# USB3_Controller_Schematics.net
KiCad netlist of a schematic drawn in Altium Designer
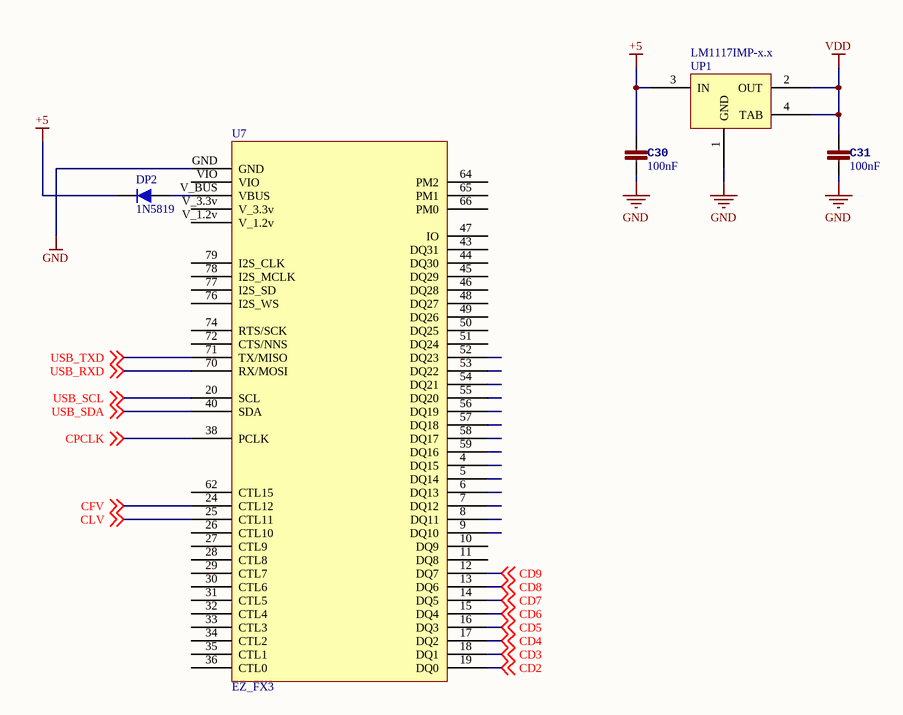
[diagram p0: USB3_Controller_Schematics.SchDoc]

(export (version "E")
  (design (tool "Eeschema 10.0.6"))
  (components
    (comp (ref "C30")
      (value "100nF")
      (footprint "_0805")
      (fields (field (name "Comment") "Cap"))
      (libsource (lib "Passives_Integrated_Library") (part "Cap_1"))
    )
    (comp (ref "C31")
      (value "100nF")
      (footprint "_0805")
      (fields (field (name "Comment") "Cap"))
      (libsource (lib "Passives_Integrated_Library") (part "Cap_1"))
    )
    (comp (ref "DP2")
      (value "1N5819")
      (footprint "430X270D")
      (description "Schottkey Rectifiers")
      (fields (field (name "DESIGNER") "Abbas Basereh"))
      (libsource (lib "Diodes_Integrated_Library") (part "1N5819"))
    )
    (comp (ref "U7")
      (value "EZ_FX3")
      (footprint "EZ_FX3")
      (libsource (lib "Boards_ans_moduls_Integrated_Library") (part "EZ_FX3"))
    )
    (comp (ref "UP1")
      (value "LM1117IMP-x.x")
      (footprint "SOT223_4")
      (description "x.x Volt, 800mA Low-Dropout Linear Regulator, 4-pin SOT-223")
      (fields (field (name "DESIGNER") "Abbas Basereh"))
      (libsource (lib "Regulators_Integrated_Library") (part "LM1117IMP-x.x"))
    )
  )
  (nets
    (net (code "1") (name "+5") (class "Default")
      (node (ref "C30") (pin "1") (pinfunction "1_1") (pintype "passive"))
      (node (ref "DP2") (pin "2") (pintype "passive"))
      (node (ref "UP1") (pin "3") (pinfunction "IN_3") (pintype "power_in"))
    )
    (net (code "2") (name "CD2") (class "Default")
      (node (ref "U7") (pin "19") (pinfunction "DQ0_19") (pintype "passive"))
    )
    (net (code "3") (name "CD3") (class "Default")
      (node (ref "U7") (pin "18") (pinfunction "DQ1_18") (pintype "passive"))
    )
    (net (code "4") (name "CD4") (class "Default")
      (node (ref "U7") (pin "17") (pinfunction "DQ2_17") (pintype "passive"))
    )
    (net (code "5") (name "CD5") (class "Default")
      (node (ref "U7") (pin "16") (pinfunction "DQ3_16") (pintype "passive"))
    )
    (net (code "6") (name "CD6") (class "Default")
      (node (ref "U7") (pin "15") (pinfunction "DQ4_15") (pintype "passive"))
    )
    (net (code "7") (name "CD7") (class "Default")
      (node (ref "U7") (pin "14") (pinfunction "DQ5_14") (pintype "passive"))
    )
    (net (code "8") (name "CD8") (class "Default")
      (node (ref "U7") (pin "13") (pinfunction "DQ6_13") (pintype "passive"))
    )
    (net (code "9") (name "CD9") (class "Default")
      (node (ref "U7") (pin "12") (pinfunction "DQ7_12") (pintype "passive"))
    )
    (net (code "10") (name "CFV") (class "Default")
      (node (ref "U7") (pin "24") (pinfunction "CTL12_24") (pintype "passive"))
    )
    (net (code "11") (name "CLV") (class "Default")
      (node (ref "U7") (pin "25") (pinfunction "CTL11_25") (pintype "passive"))
    )
    (net (code "12") (name "CPCLK") (class "Default")
      (node (ref "U7") (pin "38") (pinfunction "PCLK_38") (pintype "passive"))
    )
    (net (code "13") (name "GND") (class "Default")
      (node (ref "C30") (pin "2") (pinfunction "2_2") (pintype "passive"))
      (node (ref "C31") (pin "2") (pinfunction "2_2") (pintype "passive"))
      (node (ref "U7") (pin "GND") (pinfunction "GND_GND") (pintype "passive"))
      (node (ref "UP1") (pin "1") (pinfunction "GND_1") (pintype "power_in"))
    )
    (net (code "14") (name "Net-(U7-VBUS)") (class "Default")
      (node (ref "DP2") (pin "1") (pintype "passive"))
      (node (ref "U7") (pin "V_BUS") (pinfunction "VBUS_V_BUS") (pintype "passive"))
    )
    (net (code "15") (name "USB_RXD") (class "Default")
      (node (ref "U7") (pin "70") (pinfunction "RX/MOSI_70") (pintype "passive"))
    )
    (net (code "16") (name "USB_SCL") (class "Default")
      (node (ref "U7") (pin "20") (pinfunction "SCL_20") (pintype "passive"))
    )
    (net (code "17") (name "USB_SDA") (class "Default")
      (node (ref "U7") (pin "40") (pinfunction "SDA_40") (pintype "passive"))
    )
    (net (code "18") (name "USB_TXD") (class "Default")
      (node (ref "U7") (pin "71") (pinfunction "TX/MISO_71") (pintype "passive"))
    )
    (net (code "19") (name "VDD") (class "Default")
      (node (ref "C31") (pin "1") (pinfunction "1_1") (pintype "passive"))
      (node (ref "UP1") (pin "2") (pinfunction "OUT_2") (pintype "power_in"))
      (node (ref "UP1") (pin "4") (pinfunction "TAB_4") (pintype "power_in"))
    )
    (net (code "20") (name "unconnected-(U7-CTL0-Pad36)") (class "Default")
      (node (ref "U7") (pin "36") (pinfunction "CTL0_36") (pintype "passive"))
    )
    (net (code "21") (name "unconnected-(U7-CTL1-Pad35)") (class "Default")
      (node (ref "U7") (pin "35") (pinfunction "CTL1_35") (pintype "passive"))
    )
    (net (code "22") (name "unconnected-(U7-CTL2-Pad34)") (class "Default")
      (node (ref "U7") (pin "34") (pinfunction "CTL2_34") (pintype "passive"))
    )
    (net (code "23") (name "unconnected-(U7-CTL3-Pad33)") (class "Default")
      (node (ref "U7") (pin "33") (pinfunction "CTL3_33") (pintype "passive"))
    )
    (net (code "24") (name "unconnected-(U7-CTL4-Pad32)") (class "Default")
      (node (ref "U7") (pin "32") (pinfunction "CTL4_32") (pintype "passive"))
    )
    (net (code "25") (name "unconnected-(U7-CTL5-Pad31)") (class "Default")
      (node (ref "U7") (pin "31") (pinfunction "CTL5_31") (pintype "passive"))
    )
    (net (code "26") (name "unconnected-(U7-CTL6-Pad30)") (class "Default")
      (node (ref "U7") (pin "30") (pinfunction "CTL6_30") (pintype "passive"))
    )
    (net (code "27") (name "unconnected-(U7-CTL7-Pad29)") (class "Default")
      (node (ref "U7") (pin "29") (pinfunction "CTL7_29") (pintype "passive"))
    )
    (net (code "28") (name "unconnected-(U7-CTL8-Pad28)") (class "Default")
      (node (ref "U7") (pin "28") (pinfunction "CTL8_28") (pintype "passive"))
    )
    (net (code "29") (name "unconnected-(U7-CTL9-Pad27)") (class "Default")
      (node (ref "U7") (pin "27") (pinfunction "CTL9_27") (pintype "passive"))
    )
    (net (code "30") (name "unconnected-(U7-CTL10-Pad26)") (class "Default")
      (node (ref "U7") (pin "26") (pinfunction "CTL10_26") (pintype "passive"))
    )
    (net (code "31") (name "unconnected-(U7-CTL15-Pad62)") (class "Default")
      (node (ref "U7") (pin "62") (pinfunction "CTL15_62") (pintype "passive"))
    )
    (net (code "32") (name "unconnected-(U7-CTS{slash}NNS-Pad72)") (class "Default")
      (node (ref "U7") (pin "72") (pinfunction "CTS/NNS_72") (pintype "passive"))
    )
    (net (code "33") (name "unconnected-(U7-DQ8-Pad11)") (class "Default")
      (node (ref "U7") (pin "11") (pinfunction "DQ8_11") (pintype "passive"))
    )
    (net (code "34") (name "unconnected-(U7-DQ9-Pad10)") (class "Default")
      (node (ref "U7") (pin "10") (pinfunction "DQ9_10") (pintype "passive"))
    )
    (net (code "35") (name "unconnected-(U7-DQ10-Pad9)") (class "Default")
      (node (ref "U7") (pin "9") (pinfunction "DQ10_9") (pintype "passive"))
    )
    (net (code "36") (name "unconnected-(U7-DQ11-Pad8)") (class "Default")
      (node (ref "U7") (pin "8") (pinfunction "DQ11_8") (pintype "passive"))
    )
    (net (code "37") (name "unconnected-(U7-DQ12-Pad7)") (class "Default")
      (node (ref "U7") (pin "7") (pinfunction "DQ12_7") (pintype "passive"))
    )
    (net (code "38") (name "unconnected-(U7-DQ13-Pad6)") (class "Default")
      (node (ref "U7") (pin "6") (pinfunction "DQ13_6") (pintype "passive"))
    )
    (net (code "39") (name "unconnected-(U7-DQ14-Pad5)") (class "Default")
      (node (ref "U7") (pin "5") (pinfunction "DQ14_5") (pintype "passive"))
    )
    (net (code "40") (name "unconnected-(U7-DQ15-Pad4)") (class "Default")
      (node (ref "U7") (pin "4") (pinfunction "DQ15_4") (pintype "passive"))
    )
    (net (code "41") (name "unconnected-(U7-DQ16-Pad59)") (class "Default")
      (node (ref "U7") (pin "59") (pinfunction "DQ16_59") (pintype "passive"))
    )
    (net (code "42") (name "unconnected-(U7-DQ17-Pad58)") (class "Default")
      (node (ref "U7") (pin "58") (pinfunction "DQ17_58") (pintype "passive"))
    )
    (net (code "43") (name "unconnected-(U7-DQ18-Pad57)") (class "Default")
      (node (ref "U7") (pin "57") (pinfunction "DQ18_57") (pintype "passive"))
    )
    (net (code "44") (name "unconnected-(U7-DQ19-Pad56)") (class "Default")
      (node (ref "U7") (pin "56") (pinfunction "DQ19_56") (pintype "passive"))
    )
    (net (code "45") (name "unconnected-(U7-DQ20-Pad55)") (class "Default")
      (node (ref "U7") (pin "55") (pinfunction "DQ20_55") (pintype "passive"))
    )
    (net (code "46") (name "unconnected-(U7-DQ21-Pad54)") (class "Default")
      (node (ref "U7") (pin "54") (pinfunction "DQ21_54") (pintype "passive"))
    )
    (net (code "47") (name "unconnected-(U7-DQ22-Pad53)") (class "Default")
      (node (ref "U7") (pin "53") (pinfunction "DQ22_53") (pintype "passive"))
    )
    (net (code "48") (name "unconnected-(U7-DQ23-Pad52)") (class "Default")
      (node (ref "U7") (pin "52") (pinfunction "DQ23_52") (pintype "passive"))
    )
    (net (code "49") (name "unconnected-(U7-DQ24-Pad51)") (class "Default")
      (node (ref "U7") (pin "51") (pinfunction "DQ24_51") (pintype "passive"))
    )
    (net (code "50") (name "unconnected-(U7-DQ25-Pad50)") (class "Default")
      (node (ref "U7") (pin "50") (pinfunction "DQ25_50") (pintype "passive"))
    )
    (net (code "51") (name "unconnected-(U7-DQ26-Pad49)") (class "Default")
      (node (ref "U7") (pin "49") (pinfunction "DQ26_49") (pintype "passive"))
    )
    (net (code "52") (name "unconnected-(U7-DQ27-Pad48)") (class "Default")
      (node (ref "U7") (pin "48") (pinfunction "DQ27_48") (pintype "passive"))
    )
    (net (code "53") (name "unconnected-(U7-DQ28-Pad46)") (class "Default")
      (node (ref "U7") (pin "46") (pinfunction "DQ28_46") (pintype "passive"))
    )
    (net (code "54") (name "unconnected-(U7-DQ29-Pad45)") (class "Default")
      (node (ref "U7") (pin "45") (pinfunction "DQ29_45") (pintype "passive"))
    )
    (net (code "55") (name "unconnected-(U7-DQ30-Pad44)") (class "Default")
      (node (ref "U7") (pin "44") (pinfunction "DQ30_44") (pintype "passive"))
    )
    (net (code "56") (name "unconnected-(U7-DQ31-Pad43)") (class "Default")
      (node (ref "U7") (pin "43") (pinfunction "DQ31_43") (pintype "passive"))
    )
    (net (code "57") (name "unconnected-(U7-I2S_CLK-Pad79)") (class "Default")
      (node (ref "U7") (pin "79") (pinfunction "I2S_CLK_79") (pintype "passive"))
    )
    (net (code "58") (name "unconnected-(U7-I2S_MCLK-Pad78)") (class "Default")
      (node (ref "U7") (pin "78") (pinfunction "I2S_MCLK_78") (pintype "passive"))
    )
    (net (code "59") (name "unconnected-(U7-I2S_SD-Pad77)") (class "Default")
      (node (ref "U7") (pin "77") (pinfunction "I2S_SD_77") (pintype "passive"))
    )
    (net (code "60") (name "unconnected-(U7-I2S_WS-Pad76)") (class "Default")
      (node (ref "U7") (pin "76") (pinfunction "I2S_WS_76") (pintype "passive"))
    )
    (net (code "61") (name "unconnected-(U7-IO-Pad47)") (class "Default")
      (node (ref "U7") (pin "47") (pinfunction "IO_47") (pintype "passive"))
    )
    (net (code "62") (name "unconnected-(U7-PM0-Pad66)") (class "Default")
      (node (ref "U7") (pin "66") (pinfunction "PM0_66") (pintype "passive"))
    )
    (net (code "63") (name "unconnected-(U7-PM1-Pad65)") (class "Default")
      (node (ref "U7") (pin "65") (pinfunction "PM1_65") (pintype "passive"))
    )
    (net (code "64") (name "unconnected-(U7-PM2-Pad64)") (class "Default")
      (node (ref "U7") (pin "64") (pinfunction "PM2_64") (pintype "passive"))
    )
    (net (code "65") (name "unconnected-(U7-PadVIO)") (class "Default")
      (node (ref "U7") (pin "VIO") (pinfunction "VIO_VIO") (pintype "passive"))
    )
    (net (code "66") (name "unconnected-(U7-PadV_1.2v)") (class "Default")
      (node (ref "U7") (pin "V_1.2v") (pinfunction "V_1.2v_V_1.2v") (pintype "passive"))
    )
    (net (code "67") (name "unconnected-(U7-PadV_3.3v)") (class "Default")
      (node (ref "U7") (pin "V_3.3v") (pinfunction "V_3.3v_V_3.3v") (pintype "passive"))
    )
    (net (code "68") (name "unconnected-(U7-RTS{slash}SCK-Pad74)") (class "Default")
      (node (ref "U7") (pin "74") (pinfunction "RTS/SCK_74") (pintype "passive"))
    )
  )
)
